# EnsembleOne.net
KiCad netlist of a schematic drawn in EAGLE
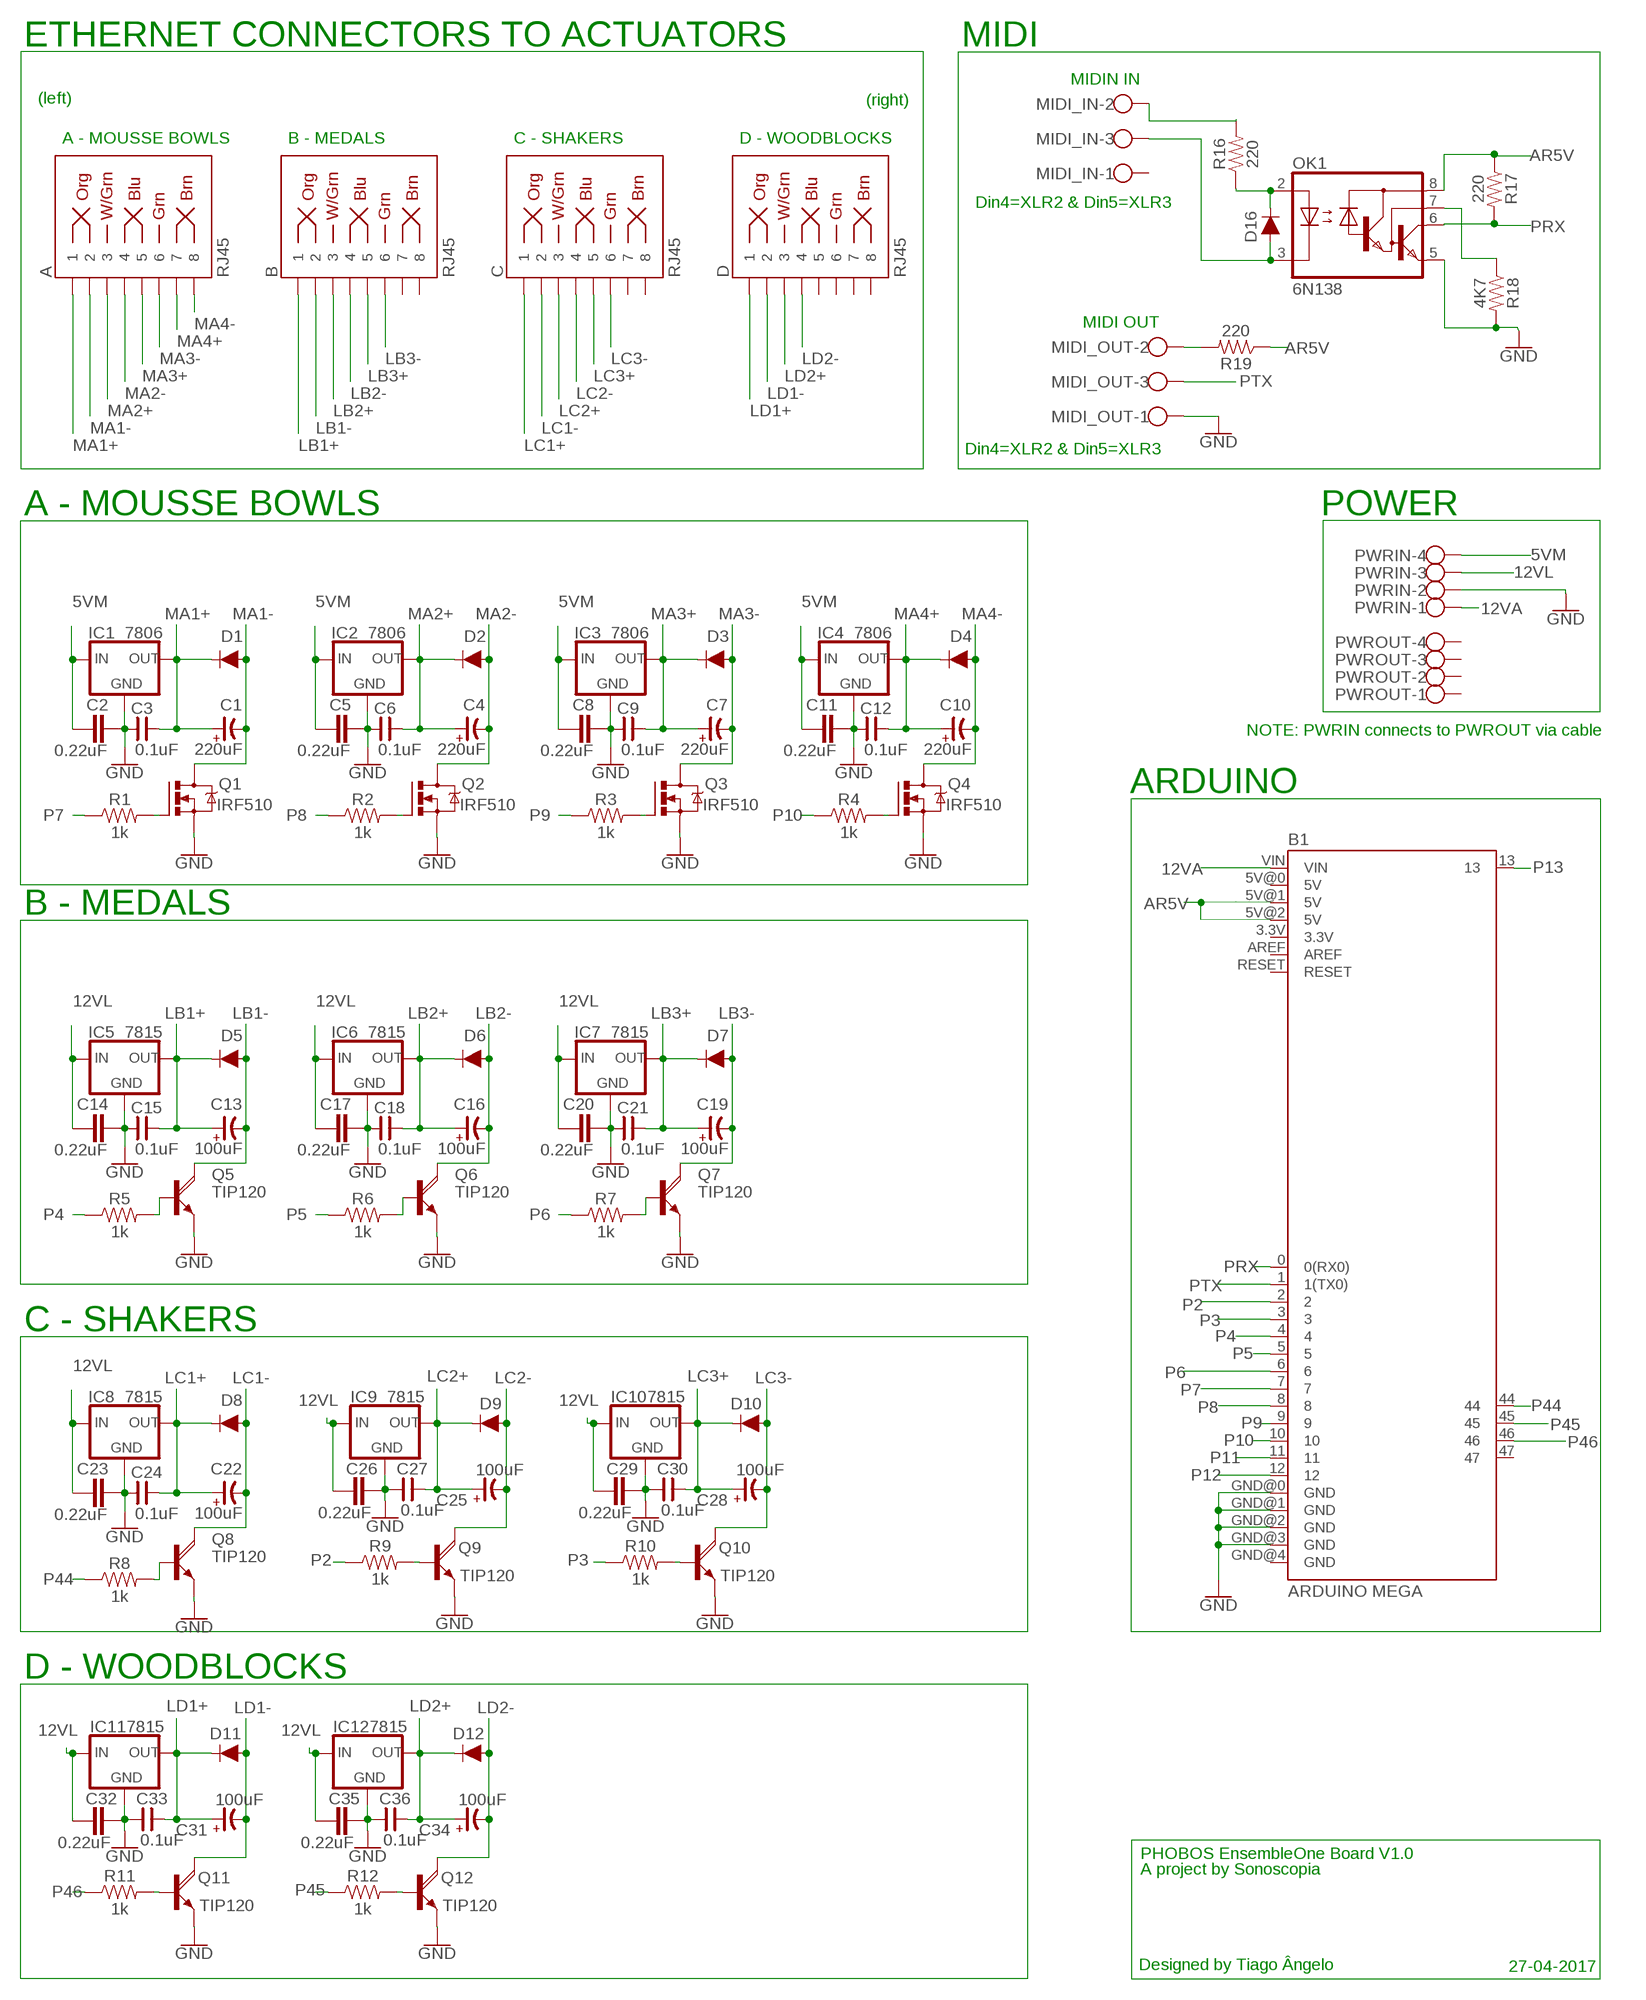
[diagram p0: schematic, sheet 1]

(export (version "E")
  (design (tool "Eeschema 10.0.6"))
  (components
    (comp (ref "A")
      (value "RJ45")
      (footprint "eagle-import:RJ45-8")
      (libsource (lib "eagle-import") (part "RJ45-8"))
    )
    (comp (ref "B")
      (value "RJ45")
      (footprint "eagle-import:RJ45-8")
      (libsource (lib "eagle-import") (part "RJ45-8"))
    )
    (comp (ref "B1")
      (value "ARDUINO MEGA")
      (footprint "eagle-import:ENSEMBLE_ONE_ARDUINO_MEGA")
      (libsource (lib "eagle-import") (part "ENSEMBLE_ONE_ARDUINO_MEGA_R3"))
    )
    (comp (ref "C")
      (value "RJ45")
      (footprint "eagle-import:RJ45-8")
      (libsource (lib "eagle-import") (part "RJ45-8"))
    )
    (comp (ref "C1")
      (value "220uF")
      (footprint "eagle-import:E-035X080")
      (libsource (lib "eagle-import") (part "CP-E-035X080"))
    )
    (comp (ref "C2")
      (value "0.22uF")
      (footprint "eagle-import:C5B3")
      (libsource (lib "eagle-import") (part "C5/3"))
    )
    (comp (ref "C3")
      (value "0.1uF")
      (footprint "eagle-import:C025-050X025")
      (libsource (lib "eagle-import") (part "CNP-C025-050X025"))
    )
    (comp (ref "C4")
      (value "220uF")
      (footprint "eagle-import:E-035X080")
      (libsource (lib "eagle-import") (part "CP-E-035X080"))
    )
    (comp (ref "C5")
      (value "0.22uF")
      (footprint "eagle-import:C5B3")
      (libsource (lib "eagle-import") (part "C5/3"))
    )
    (comp (ref "C6")
      (value "0.1uF")
      (footprint "eagle-import:C025-050X025")
      (libsource (lib "eagle-import") (part "CNP-C025-050X025"))
    )
    (comp (ref "C7")
      (value "220uF")
      (footprint "eagle-import:E-035X080")
      (libsource (lib "eagle-import") (part "CP-E-035X080"))
    )
    (comp (ref "C8")
      (value "0.22uF")
      (footprint "eagle-import:C5B3")
      (libsource (lib "eagle-import") (part "C5/3"))
    )
    (comp (ref "C9")
      (value "0.1uF")
      (footprint "eagle-import:C025-050X025")
      (libsource (lib "eagle-import") (part "CNP-C025-050X025"))
    )
    (comp (ref "C10")
      (value "220uF")
      (footprint "eagle-import:E-035X080")
      (libsource (lib "eagle-import") (part "CP-E-035X080"))
    )
    (comp (ref "C11")
      (value "0.22uF")
      (footprint "eagle-import:C5B3")
      (libsource (lib "eagle-import") (part "C5/3"))
    )
    (comp (ref "C12")
      (value "0.1uF")
      (footprint "eagle-import:C025-050X025")
      (libsource (lib "eagle-import") (part "CNP-C025-050X025"))
    )
    (comp (ref "C13")
      (value "100uF")
      (footprint "eagle-import:CAP-MASTER_E-020X050")
      (libsource (lib "eagle-import") (part "CAP-MASTER_CP-E-020X050"))
    )
    (comp (ref "C14")
      (value "0.22uF")
      (footprint "eagle-import:C5B3")
      (libsource (lib "eagle-import") (part "C5/3"))
    )
    (comp (ref "C15")
      (value "0.1uF")
      (footprint "eagle-import:C025-050X025")
      (libsource (lib "eagle-import") (part "CNP-C025-050X025"))
    )
    (comp (ref "C16")
      (value "100uF")
      (footprint "eagle-import:CAP-MASTER_E-020X050")
      (libsource (lib "eagle-import") (part "CAP-MASTER_CP-E-020X050"))
    )
    (comp (ref "C17")
      (value "0.22uF")
      (footprint "eagle-import:C5B3")
      (libsource (lib "eagle-import") (part "C5/3"))
    )
    (comp (ref "C18")
      (value "0.1uF")
      (footprint "eagle-import:C025-050X025")
      (libsource (lib "eagle-import") (part "CNP-C025-050X025"))
    )
    (comp (ref "C19")
      (value "100uF")
      (footprint "eagle-import:CAP-MASTER_E-020X050")
      (libsource (lib "eagle-import") (part "CAP-MASTER_CP-E-020X050"))
    )
    (comp (ref "C20")
      (value "0.22uF")
      (footprint "eagle-import:C5B3")
      (libsource (lib "eagle-import") (part "C5/3"))
    )
    (comp (ref "C21")
      (value "0.1uF")
      (footprint "eagle-import:C025-050X025")
      (libsource (lib "eagle-import") (part "CNP-C025-050X025"))
    )
    (comp (ref "C22")
      (value "100uF")
      (footprint "eagle-import:CAP-MASTER_E-020X050")
      (libsource (lib "eagle-import") (part "CAP-MASTER_CP-E-020X050"))
    )
    (comp (ref "C23")
      (value "0.22uF")
      (footprint "eagle-import:C5B3")
      (libsource (lib "eagle-import") (part "C5/3"))
    )
    (comp (ref "C24")
      (value "0.1uF")
      (footprint "eagle-import:C025-050X025")
      (libsource (lib "eagle-import") (part "CNP-C025-050X025"))
    )
    (comp (ref "C25")
      (value "100uF")
      (footprint "eagle-import:E-020X050")
      (libsource (lib "eagle-import") (part "CP-E-020X050"))
    )
    (comp (ref "C26")
      (value "0.22uF")
      (footprint "eagle-import:C5B3")
      (libsource (lib "eagle-import") (part "C5/3"))
    )
    (comp (ref "C27")
      (value "0.1uF")
      (footprint "eagle-import:C025-050X025")
      (libsource (lib "eagle-import") (part "CNP-C025-050X025"))
    )
    (comp (ref "C28")
      (value "100uF")
      (footprint "eagle-import:E-020X050")
      (libsource (lib "eagle-import") (part "CP-E-020X050"))
    )
    (comp (ref "C29")
      (value "0.22uF")
      (footprint "eagle-import:C5B3")
      (libsource (lib "eagle-import") (part "C5/3"))
    )
    (comp (ref "C30")
      (value "0.1uF")
      (footprint "eagle-import:C025-050X025")
      (libsource (lib "eagle-import") (part "CNP-C025-050X025"))
    )
    (comp (ref "C31")
      (value "100uF")
      (footprint "eagle-import:E-020X050")
      (libsource (lib "eagle-import") (part "CP-E-020X050"))
    )
    (comp (ref "C32")
      (value "0.22uF")
      (footprint "eagle-import:C5B3")
      (libsource (lib "eagle-import") (part "C5/3"))
    )
    (comp (ref "C33")
      (value "0.1uF")
      (footprint "eagle-import:C025-050X025")
      (libsource (lib "eagle-import") (part "CNP-C025-050X025"))
    )
    (comp (ref "C34")
      (value "100uF")
      (footprint "eagle-import:E-020X050")
      (libsource (lib "eagle-import") (part "CP-E-020X050"))
    )
    (comp (ref "C35")
      (value "0.22uF")
      (footprint "eagle-import:C5B3")
      (libsource (lib "eagle-import") (part "C5/3"))
    )
    (comp (ref "C36")
      (value "0.1uF")
      (footprint "eagle-import:C025-050X025")
      (libsource (lib "eagle-import") (part "CNP-C025-050X025"))
    )
    (comp (ref "D")
      (value "RJ45")
      (footprint "eagle-import:RJ45-8")
      (libsource (lib "eagle-import") (part "RJ45-8"))
    )
    (comp (ref "D1")
      (value "1A/50V/1.1V")
      (footprint "eagle-import:DIODE-1N4001-KIT")
      (libsource (lib "eagle-import") (part "DIODE-KIT2"))
    )
    (comp (ref "D2")
      (value "1A/50V/1.1V")
      (footprint "eagle-import:DIODE-1N4001-KIT")
      (libsource (lib "eagle-import") (part "DIODE-KIT2"))
    )
    (comp (ref "D3")
      (value "1A/50V/1.1V")
      (footprint "eagle-import:DIODE-1N4001-KIT")
      (libsource (lib "eagle-import") (part "DIODE-KIT2"))
    )
    (comp (ref "D4")
      (value "1A/50V/1.1V")
      (footprint "eagle-import:DIODE-1N4001-KIT")
      (libsource (lib "eagle-import") (part "DIODE-KIT2"))
    )
    (comp (ref "D5")
      (value "1A/50V/1.1V")
      (footprint "eagle-import:DIODE-1N4001-KIT")
      (libsource (lib "eagle-import") (part "DIODE-KIT2"))
    )
    (comp (ref "D6")
      (value "1A/50V/1.1V")
      (footprint "eagle-import:DIODE-1N4001-KIT")
      (libsource (lib "eagle-import") (part "DIODE-KIT2"))
    )
    (comp (ref "D7")
      (value "1A/50V/1.1V")
      (footprint "eagle-import:DIODE-1N4001-KIT")
      (libsource (lib "eagle-import") (part "DIODE-KIT2"))
    )
    (comp (ref "D8")
      (value "1A/50V/1.1V")
      (footprint "eagle-import:DIODE-1N4001-KIT")
      (libsource (lib "eagle-import") (part "DIODE-KIT2"))
    )
    (comp (ref "D9")
      (value "1A/50V/1.1V")
      (footprint "eagle-import:DIODE-1N4001-KIT")
      (libsource (lib "eagle-import") (part "DIODE-KIT2"))
    )
    (comp (ref "D10")
      (value "1A/50V/1.1V")
      (footprint "eagle-import:DIODE-1N4001-KIT")
      (libsource (lib "eagle-import") (part "DIODE-KIT2"))
    )
    (comp (ref "D11")
      (value "1A/50V/1.1V")
      (footprint "eagle-import:DIODE-1N4001-KIT")
      (libsource (lib "eagle-import") (part "DIODE-KIT2"))
    )
    (comp (ref "D12")
      (value "1A/50V/1.1V")
      (footprint "eagle-import:DIODE-1N4001-KIT")
      (libsource (lib "eagle-import") (part "DIODE-KIT2"))
    )
    (comp (ref "D16")
      (value "200mA/100V/1V")
      (footprint "eagle-import:DIODE-1N4148")
      (libsource (lib "eagle-import") (part "DIODE-1N4148"))
    )
    (comp (ref "IC1")
      (value "7806")
      (footprint "eagle-import:78XXS")
      (libsource (lib "eagle-import") (part "78XXS"))
    )
    (comp (ref "IC2")
      (value "7806")
      (footprint "eagle-import:78XXS")
      (libsource (lib "eagle-import") (part "78XXS"))
    )
    (comp (ref "IC3")
      (value "7806")
      (footprint "eagle-import:78XXS")
      (libsource (lib "eagle-import") (part "78XXS"))
    )
    (comp (ref "IC4")
      (value "7806")
      (footprint "eagle-import:78XXS")
      (libsource (lib "eagle-import") (part "78XXS"))
    )
    (comp (ref "IC5")
      (value "7815")
      (footprint "eagle-import:78XXS")
      (libsource (lib "eagle-import") (part "78XXS"))
    )
    (comp (ref "IC6")
      (value "7815")
      (footprint "eagle-import:78XXS")
      (libsource (lib "eagle-import") (part "78XXS"))
    )
    (comp (ref "IC7")
      (value "7815")
      (footprint "eagle-import:78XXS")
      (libsource (lib "eagle-import") (part "78XXS"))
    )
    (comp (ref "IC8")
      (value "7815")
      (footprint "eagle-import:78XXS")
      (libsource (lib "eagle-import") (part "78XXS"))
    )
    (comp (ref "IC9")
      (value "7815")
      (footprint "eagle-import:78XXS")
      (libsource (lib "eagle-import") (part "78XXS"))
    )
    (comp (ref "IC10")
      (value "7815")
      (footprint "eagle-import:78XXS")
      (libsource (lib "eagle-import") (part "78XXS"))
    )
    (comp (ref "IC11")
      (value "7815")
      (footprint "eagle-import:78XXS")
      (libsource (lib "eagle-import") (part "78XXS"))
    )
    (comp (ref "IC12")
      (value "7815")
      (footprint "eagle-import:78XXS")
      (libsource (lib "eagle-import") (part "78XXS"))
    )
    (comp (ref "MIDI_IN")
      (value "W237-103")
      (footprint "eagle-import:W237-103")
      (fields (field (name "MPN") "237-103"))
      (libsource (lib "eagle-import") (part "W237-103"))
    )
    (comp (ref "MIDI_OUT")
      (value "W237-103")
      (footprint "eagle-import:W237-103")
      (fields (field (name "MPN") "237-103"))
      (libsource (lib "eagle-import") (part "W237-103"))
    )
    (comp (ref "OK1")
      (value "6N138")
      (footprint "eagle-import:DIL08")
      (fields (field (name "MF") "VISHAY/TELEFUNKEN"))
      (libsource (lib "eagle-import") (part "6N138"))
    )
    (comp (ref "PWRIN")
      (value "W237-4")
      (footprint "eagle-import:W237-4")
      (libsource (lib "eagle-import") (part "W237-4"))
    )
    (comp (ref "PWROUT")
      (value "W237-4")
      (footprint "eagle-import:W237-4")
      (libsource (lib "eagle-import") (part "W237-4"))
    )
    (comp (ref "Q1")
      (value "IRF510")
      (footprint "eagle-import:TO220BV")
      (libsource (lib "eagle-import") (part "IRF520"))
    )
    (comp (ref "Q2")
      (value "IRF510")
      (footprint "eagle-import:TO220BV")
      (libsource (lib "eagle-import") (part "IRF520"))
    )
    (comp (ref "Q3")
      (value "IRF510")
      (footprint "eagle-import:TO220BV")
      (libsource (lib "eagle-import") (part "IRF520"))
    )
    (comp (ref "Q4")
      (value "IRF510")
      (footprint "eagle-import:TO220BV")
      (libsource (lib "eagle-import") (part "IRF520"))
    )
    (comp (ref "Q5")
      (value "TIP120")
      (footprint "eagle-import:ROCKETFARM_TO220AV")
      (libsource (lib "eagle-import") (part "ROCKETFARM_TIP120V"))
    )
    (comp (ref "Q6")
      (value "TIP120")
      (footprint "eagle-import:ROCKETFARM_TO220AV")
      (libsource (lib "eagle-import") (part "ROCKETFARM_TIP120V"))
    )
    (comp (ref "Q7")
      (value "TIP120")
      (footprint "eagle-import:ROCKETFARM_TO220AV")
      (libsource (lib "eagle-import") (part "ROCKETFARM_TIP120V"))
    )
    (comp (ref "Q8")
      (value "TIP120")
      (footprint "eagle-import:ROCKETFARM_TO220AV")
      (libsource (lib "eagle-import") (part "ROCKETFARM_TIP120V"))
    )
    (comp (ref "Q9")
      (value "TIP120")
      (footprint "eagle-import:TO220AV")
      (libsource (lib "eagle-import") (part "TIP120V"))
    )
    (comp (ref "Q10")
      (value "TIP120")
      (footprint "eagle-import:TO220AV")
      (libsource (lib "eagle-import") (part "TIP120V"))
    )
    (comp (ref "Q11")
      (value "TIP120")
      (footprint "eagle-import:TO220AV")
      (libsource (lib "eagle-import") (part "TIP120V"))
    )
    (comp (ref "Q12")
      (value "TIP120")
      (footprint "eagle-import:TO220AV")
      (libsource (lib "eagle-import") (part "TIP120V"))
    )
    (comp (ref "R1")
      (value "1k")
      (footprint "eagle-import:AXIAL-0.1")
      (libsource (lib "eagle-import") (part "1KOHM-VERT-1/4W-1%"))
    )
    (comp (ref "R2")
      (value "1k")
      (footprint "eagle-import:AXIAL-0.1")
      (libsource (lib "eagle-import") (part "1KOHM-VERT-1/4W-1%"))
    )
    (comp (ref "R3")
      (value "1k")
      (footprint "eagle-import:AXIAL-0.1")
      (libsource (lib "eagle-import") (part "1KOHM-VERT-1/4W-1%"))
    )
    (comp (ref "R4")
      (value "1k")
      (footprint "eagle-import:AXIAL-0.1")
      (libsource (lib "eagle-import") (part "1KOHM-VERT-1/4W-1%"))
    )
    (comp (ref "R5")
      (value "1k")
      (footprint "eagle-import:AXIAL-0.1")
      (libsource (lib "eagle-import") (part "1KOHM-VERT-1/4W-1%"))
    )
    (comp (ref "R6")
      (value "1k")
      (footprint "eagle-import:AXIAL-0.1")
      (libsource (lib "eagle-import") (part "1KOHM-VERT-1/4W-1%"))
    )
    (comp (ref "R7")
      (value "1k")
      (footprint "eagle-import:AXIAL-0.1")
      (libsource (lib "eagle-import") (part "1KOHM-VERT-1/4W-1%"))
    )
    (comp (ref "R8")
      (value "1k")
      (footprint "eagle-import:AXIAL-0.1")
      (libsource (lib "eagle-import") (part "1KOHM-VERT-1/4W-1%"))
    )
    (comp (ref "R9")
      (value "1k")
      (footprint "eagle-import:AXIAL-0.1")
      (libsource (lib "eagle-import") (part "1KOHM-VERT-1/4W-1%"))
    )
    (comp (ref "R10")
      (value "1k")
      (footprint "eagle-import:AXIAL-0.1")
      (libsource (lib "eagle-import") (part "1KOHM-VERT-1/4W-1%"))
    )
    (comp (ref "R11")
      (value "1k")
      (footprint "eagle-import:AXIAL-0.1")
      (libsource (lib "eagle-import") (part "1KOHM-VERT-1/4W-1%"))
    )
    (comp (ref "R12")
      (value "1k")
      (footprint "eagle-import:AXIAL-0.1")
      (libsource (lib "eagle-import") (part "1KOHM-VERT-1/4W-1%"))
    )
    (comp (ref "R16")
      (value "220")
      (footprint "eagle-import:AXIAL-0.3")
      (libsource (lib "eagle-import") (part "1KOHM-HORIZ-1/4W-5%"))
    )
    (comp (ref "R17")
      (value "220")
      (footprint "eagle-import:AXIAL-0.3")
      (libsource (lib "eagle-import") (part "1KOHM-HORIZ-1/4W-5%"))
    )
    (comp (ref "R18")
      (value "4K7")
      (footprint "eagle-import:AXIAL-0.3")
      (libsource (lib "eagle-import") (part "1KOHM-HORIZ-1/4W-5%"))
    )
    (comp (ref "R19")
      (value "220")
      (footprint "eagle-import:AXIAL-0.3")
      (libsource (lib "eagle-import") (part "1KOHM-HORIZ-1/4W-5%"))
    )
  )
  (nets
    (net (code "1") (name "/5VM") (class "Default")
      (node (ref "C11") (pin "1") (pinfunction "1_1") (pintype "passive"))
      (node (ref "C2") (pin "1") (pinfunction "1_1") (pintype "passive"))
      (node (ref "C5") (pin "1") (pinfunction "1_1") (pintype "passive"))
      (node (ref "C8") (pin "1") (pinfunction "1_1") (pintype "passive"))
      (node (ref "IC1") (pin "IN") (pinfunction "IN_IN") (pintype "input"))
      (node (ref "IC2") (pin "IN") (pinfunction "IN_IN") (pintype "input"))
      (node (ref "IC3") (pin "IN") (pinfunction "IN_IN") (pintype "input"))
      (node (ref "IC4") (pin "IN") (pinfunction "IN_IN") (pintype "input"))
      (node (ref "PWRIN") (pin "4") (pinfunction "KL_4") (pintype "passive"))
    )
    (net (code "2") (name "/12VA") (class "Default")
      (node (ref "B1") (pin "VIN") (pinfunction "VIN_VIN") (pintype "bidirectional"))
      (node (ref "PWRIN") (pin "1") (pinfunction "KL_1") (pintype "passive"))
    )
    (net (code "3") (name "/12VL") (class "Default")
      (node (ref "C14") (pin "1") (pinfunction "1_1") (pintype "passive"))
      (node (ref "C17") (pin "1") (pinfunction "1_1") (pintype "passive"))
      (node (ref "C20") (pin "1") (pinfunction "1_1") (pintype "passive"))
      (node (ref "C23") (pin "1") (pinfunction "1_1") (pintype "passive"))
      (node (ref "C26") (pin "1") (pinfunction "1_1") (pintype "passive"))
      (node (ref "C29") (pin "1") (pinfunction "1_1") (pintype "passive"))
      (node (ref "C32") (pin "1") (pinfunction "1_1") (pintype "passive"))
      (node (ref "C35") (pin "1") (pinfunction "1_1") (pintype "passive"))
      (node (ref "IC10") (pin "IN") (pinfunction "IN_IN") (pintype "input"))
      (node (ref "IC11") (pin "IN") (pinfunction "IN_IN") (pintype "input"))
      (node (ref "IC12") (pin "IN") (pinfunction "IN_IN") (pintype "input"))
      (node (ref "IC5") (pin "IN") (pinfunction "IN_IN") (pintype "input"))
      (node (ref "IC6") (pin "IN") (pinfunction "IN_IN") (pintype "input"))
      (node (ref "IC7") (pin "IN") (pinfunction "IN_IN") (pintype "input"))
      (node (ref "IC8") (pin "IN") (pinfunction "IN_IN") (pintype "input"))
      (node (ref "IC9") (pin "IN") (pinfunction "IN_IN") (pintype "input"))
      (node (ref "PWRIN") (pin "3") (pinfunction "KL_3") (pintype "passive"))
    )
    (net (code "4") (name "/AR5V") (class "Default")
      (node (ref "B1") (pin "5V@1") (pinfunction "5V_5V@1") (pintype "bidirectional"))
      (node (ref "B1") (pin "5V@2") (pinfunction "5V_5V@2") (pintype "bidirectional"))
      (node (ref "OK1") (pin "8") (pinfunction "VCC_8") (pintype "passive"))
      (node (ref "R17") (pin "P$1") (pinfunction "1_P$1") (pintype "passive"))
      (node (ref "R19") (pin "P$1") (pinfunction "1_P$1") (pintype "passive"))
    )
    (net (code "5") (name "/LB1+") (class "Default")
      (node (ref "B") (pin "1") (pinfunction "1_1") (pintype "bidirectional"))
      (node (ref "C13") (pin "+") (pinfunction "+_+") (pintype "passive"))
      (node (ref "C15") (pin "2") (pinfunction "2_2") (pintype "passive"))
      (node (ref "D5") (pin "C") (pinfunction "C_C") (pintype "passive"))
      (node (ref "IC5") (pin "OUT") (pinfunction "OUT_OUT") (pintype "passive"))
    )
    (net (code "6") (name "/LB1-") (class "Default")
      (node (ref "B") (pin "2") (pinfunction "2_2") (pintype "bidirectional"))
      (node (ref "C13") (pin "-") (pinfunction "-_-") (pintype "passive"))
      (node (ref "D5") (pin "A") (pinfunction "A_A") (pintype "passive"))
      (node (ref "Q5") (pin "C") (pinfunction "C_C") (pintype "passive"))
    )
    (net (code "7") (name "/LB2+") (class "Default")
      (node (ref "B") (pin "3") (pinfunction "3_3") (pintype "bidirectional"))
      (node (ref "C16") (pin "+") (pinfunction "+_+") (pintype "passive"))
      (node (ref "C18") (pin "2") (pinfunction "2_2") (pintype "passive"))
      (node (ref "D6") (pin "C") (pinfunction "C_C") (pintype "passive"))
      (node (ref "IC6") (pin "OUT") (pinfunction "OUT_OUT") (pintype "passive"))
    )
    (net (code "8") (name "/LB2-") (class "Default")
      (node (ref "B") (pin "4") (pinfunction "4_4") (pintype "bidirectional"))
      (node (ref "C16") (pin "-") (pinfunction "-_-") (pintype "passive"))
      (node (ref "D6") (pin "A") (pinfunction "A_A") (pintype "passive"))
      (node (ref "Q6") (pin "C") (pinfunction "C_C") (pintype "passive"))
    )
    (net (code "9") (name "/LB3+") (class "Default")
      (node (ref "B") (pin "5") (pinfunction "5_5") (pintype "bidirectional"))
      (node (ref "C19") (pin "+") (pinfunction "+_+") (pintype "passive"))
      (node (ref "C21") (pin "2") (pinfunction "2_2") (pintype "passive"))
      (node (ref "D7") (pin "C") (pinfunction "C_C") (pintype "passive"))
      (node (ref "IC7") (pin "OUT") (pinfunction "OUT_OUT") (pintype "passive"))
    )
    (net (code "10") (name "/LB3-") (class "Default")
      (node (ref "B") (pin "6") (pinfunction "6_6") (pintype "bidirectional"))
      (node (ref "C19") (pin "-") (pinfunction "-_-") (pintype "passive"))
      (node (ref "D7") (pin "A") (pinfunction "A_A") (pintype "passive"))
      (node (ref "Q7") (pin "C") (pinfunction "C_C") (pintype "passive"))
    )
    (net (code "11") (name "/LC1+") (class "Default")
      (node (ref "C") (pin "1") (pinfunction "1_1") (pintype "bidirectional"))
      (node (ref "C22") (pin "+") (pinfunction "+_+") (pintype "passive"))
      (node (ref "C24") (pin "2") (pinfunction "2_2") (pintype "passive"))
      (node (ref "D8") (pin "C") (pinfunction "C_C") (pintype "passive"))
      (node (ref "IC8") (pin "OUT") (pinfunction "OUT_OUT") (pintype "passive"))
    )
    (net (code "12") (name "/LC1-") (class "Default")
      (node (ref "C") (pin "2") (pinfunction "2_2") (pintype "bidirectional"))
      (node (ref "C22") (pin "-") (pinfunction "-_-") (pintype "passive"))
      (node (ref "D8") (pin "A") (pinfunction "A_A") (pintype "passive"))
      (node (ref "Q8") (pin "C") (pinfunction "C_C") (pintype "passive"))
    )
    (net (code "13") (name "/LC2+") (class "Default")
      (node (ref "C") (pin "3") (pinfunction "3_3") (pintype "bidirectional"))
      (node (ref "C25") (pin "+") (pinfunction "+_+") (pintype "passive"))
      (node (ref "C27") (pin "2") (pinfunction "2_2") (pintype "passive"))
      (node (ref "D9") (pin "C") (pinfunction "C_C") (pintype "passive"))
      (node (ref "IC9") (pin "OUT") (pinfunction "OUT_OUT") (pintype "passive"))
    )
    (net (code "14") (name "/LC2-") (class "Default")
      (node (ref "C") (pin "4") (pinfunction "4_4") (pintype "bidirectional"))
      (node (ref "C25") (pin "-") (pinfunction "-_-") (pintype "passive"))
      (node (ref "D9") (pin "A") (pinfunction "A_A") (pintype "passive"))
      (node (ref "Q9") (pin "C") (pinfunction "C_C") (pintype "passive"))
    )
    (net (code "15") (name "/LC3+") (class "Default")
      (node (ref "C") (pin "5") (pinfunction "5_5") (pintype "bidirectional"))
      (node (ref "C28") (pin "+") (pinfunction "+_+") (pintype "passive"))
      (node (ref "C30") (pin "2") (pinfunction "2_2") (pintype "passive"))
      (node (ref "D10") (pin "C") (pinfunction "C_C") (pintype "passive"))
      (node (ref "IC10") (pin "OUT") (pinfunction "OUT_OUT") (pintype "passive"))
    )
    (net (code "16") (name "/LC3-") (class "Default")
      (node (ref "C") (pin "6") (pinfunction "6_6") (pintype "bidirectional"))
      (node (ref "C28") (pin "-") (pinfunction "-_-") (pintype "passive"))
      (node (ref "D10") (pin "A") (pinfunction "A_A") (pintype "passive"))
      (node (ref "Q10") (pin "C") (pinfunction "C_C") (pintype "passive"))
    )
    (net (code "17") (name "/LD1+") (class "Default")
      (node (ref "C31") (pin "+") (pinfunction "+_+") (pintype "passive"))
      (node (ref "C33") (pin "2") (pinfunction "2_2") (pintype "passive"))
      (node (ref "D") (pin "1") (pinfunction "1_1") (pintype "bidirectional"))
      (node (ref "D11") (pin "C") (pinfunction "C_C") (pintype "passive"))
      (node (ref "IC11") (pin "OUT") (pinfunction "OUT_OUT") (pintype "passive"))
    )
    (net (code "18") (name "/LD1-") (class "Default")
      (node (ref "C31") (pin "-") (pinfunction "-_-") (pintype "passive"))
      (node (ref "D") (pin "2") (pinfunction "2_2") (pintype "bidirectional"))
      (node (ref "D11") (pin "A") (pinfunction "A_A") (pintype "passive"))
      (node (ref "Q11") (pin "C") (pinfunction "C_C") (pintype "passive"))
    )
    (net (code "19") (name "/LD2+") (class "Default")
      (node (ref "C34") (pin "+") (pinfunction "+_+") (pintype "passive"))
      (node (ref "C36") (pin "2") (pinfunction "2_2") (pintype "passive"))
      (node (ref "D") (pin "3") (pinfunction "3_3") (pintype "bidirectional"))
      (node (ref "D12") (pin "C") (pinfunction "C_C") (pintype "passive"))
      (node (ref "IC12") (pin "OUT") (pinfunction "OUT_OUT") (pintype "passive"))
    )
    (net (code "20") (name "/LD2-") (class "Default")
      (node (ref "C34") (pin "-") (pinfunction "-_-") (pintype "passive"))
      (node (ref "D") (pin "4") (pinfunction "4_4") (pintype "bidirectional"))
      (node (ref "D12") (pin "A") (pinfunction "A_A") (pintype "passive"))
      (node (ref "Q12") (pin "C") (pinfunction "C_C") (pintype "passive"))
    )
    (net (code "21") (name "/MA1+") (class "Default")
      (node (ref "A") (pin "1") (pinfunction "1_1") (pintype "bidirectional"))
      (node (ref "C1") (pin "+") (pinfunction "+_+") (pintype "passive"))
      (node (ref "C3") (pin "2") (pinfunction "2_2") (pintype "passive"))
      (node (ref "D1") (pin "C") (pinfunction "C_C") (pintype "passive"))
      (node (ref "IC1") (pin "OUT") (pinfunction "OUT_OUT") (pintype "passive"))
    )
    (net (code "22") (name "/MA1-") (class "Default")
      (node (ref "A") (pin "2") (pinfunction "2_2") (pintype "bidirectional"))
      (node (ref "C1") (pin "-") (pinfunction "-_-") (pintype "passive"))
      (node (ref "D1") (pin "A") (pinfunction "A_A") (pintype "passive"))
      (node (ref "Q1") (pin "D") (pinfunction "D_D") (pintype "passive"))
    )
    (net (code "23") (name "/MA2+") (class "Default")
      (node (ref "A") (pin "3") (pinfunction "3_3") (pintype "bidirectional"))
      (node (ref "C4") (pin "+") (pinfunction "+_+") (pintype "passive"))
      (node (ref "C6") (pin "2") (pinfunction "2_2") (pintype "passive"))
      (node (ref "D2") (pin "C") (pinfunction "C_C") (pintype "passive"))
      (node (ref "IC2") (pin "OUT") (pinfunction "OUT_OUT") (pintype "passive"))
    )
    (net (code "24") (name "/MA2-") (class "Default")
      (node (ref "A") (pin "4") (pinfunction "4_4") (pintype "bidirectional"))
      (node (ref "C4") (pin "-") (pinfunction "-_-") (pintype "passive"))
      (node (ref "D2") (pin "A") (pinfunction "A_A") (pintype "passive"))
      (node (ref "Q2") (pin "D") (pinfunction "D_D") (pintype "passive"))
    )
    (net (code "25") (name "/MA3+") (class "Default")
      (node (ref "A") (pin "5") (pinfunction "5_5") (pintype "bidirectional"))
      (node (ref "C7") (pin "+") (pinfunction "+_+") (pintype "passive"))
      (node (ref "C9") (pin "2") (pinfunction "2_2") (pintype "passive"))
      (node (ref "D3") (pin "C") (pinfunction "C_C") (pintype "passive"))
      (node (ref "IC3") (pin "OUT") (pinfunction "OUT_OUT") (pintype "passive"))
    )
    (net (code "26") (name "/MA3-") (class "Default")
      (node (ref "A") (pin "6") (pinfunction "6_6") (pintype "bidirectional"))
      (node (ref "C7") (pin "-") (pinfunction "-_-") (pintype "passive"))
      (node (ref "D3") (pin "A") (pinfunction "A_A") (pintype "passive"))
      (node (ref "Q3") (pin "D") (pinfunction "D_D") (pintype "passive"))
    )
    (net (code "27") (name "/MA4+") (class "Default")
      (node (ref "A") (pin "7") (pinfunction "7_7") (pintype "bidirectional"))
      (node (ref "C10") (pin "+") (pinfunction "+_+") (pintype "passive"))
      (node (ref "C12") (pin "2") (pinfunction "2_2") (pintype "passive"))
      (node (ref "D4") (pin "C") (pinfunction "C_C") (pintype "passive"))
      (node (ref "IC4") (pin "OUT") (pinfunction "OUT_OUT") (pintype "passive"))
    )
    (net (code "28") (name "/MA4-") (class "Default")
      (node (ref "A") (pin "8") (pinfunction "8_8") (pintype "bidirectional"))
      (node (ref "C10") (pin "-") (pinfunction "-_-") (pintype "passive"))
      (node (ref "D4") (pin "A") (pinfunction "A_A") (pintype "passive"))
      (node (ref "Q4") (pin "D") (pinfunction "D_D") (pintype "passive"))
    )
    (net (code "29") (name "/P2") (class "Default")
      (node (ref "B1") (pin "2") (pinfunction "2_2") (pintype "bidirectional"))
      (node (ref "R9") (pin "P$1") (pinfunction "1_P$1") (pintype "passive"))
    )
    (net (code "30") (name "/P3") (class "Default")
      (node (ref "B1") (pin "3") (pinfunction "3_3") (pintype "bidirectional"))
      (node (ref "R10") (pin "P$1") (pinfunction "1_P$1") (pintype "passive"))
    )
    (net (code "31") (name "/P4") (class "Default")
      (node (ref "B1") (pin "4") (pinfunction "4_4") (pintype "bidirectional"))
      (node (ref "R5") (pin "P$1") (pinfunction "1_P$1") (pintype "passive"))
    )
    (net (code "32") (name "/P5") (class "Default")
      (node (ref "B1") (pin "5") (pinfunction "5_5") (pintype "bidirectional"))
      (node (ref "R6") (pin "P$1") (pinfunction "1_P$1") (pintype "passive"))
    )
    (net (code "33") (name "/P6") (class "Default")
      (node (ref "B1") (pin "6") (pinfunction "6_6") (pintype "bidirectional"))
      (node (ref "R7") (pin "P$1") (pinfunction "1_P$1") (pintype "passive"))
    )
    (net (code "34") (name "/P7") (class "Default")
      (node (ref "B1") (pin "7") (pinfunction "7_7") (pintype "bidirectional"))
      (node (ref "R1") (pin "P$1") (pinfunction "1_P$1") (pintype "passive"))
    )
    (net (code "35") (name "/P8") (class "Default")
      (node (ref "B1") (pin "8") (pinfunction "8_8") (pintype "bidirectional"))
      (node (ref "R2") (pin "P$1") (pinfunction "1_P$1") (pintype "passive"))
    )
    (net (code "36") (name "/P9") (class "Default")
      (node (ref "B1") (pin "9") (pinfunction "9_9") (pintype "bidirectional"))
      (node (ref "R3") (pin "P$1") (pinfunction "1_P$1") (pintype "passive"))
    )
    (net (code "37") (name "/P10") (class "Default")
      (node (ref "B1") (pin "10") (pinfunction "10_10") (pintype "bidirectional"))
      (node (ref "R4") (pin "P$1") (pinfunction "1_P$1") (pintype "passive"))
    )
    (net (code "38") (name "/P11") (class "Default")
      (node (ref "B1") (pin "11") (pinfunction "11_11") (pintype "bidirectional"))
    )
    (net (code "39") (name "/P12") (class "Default")
      (node (ref "B1") (pin "12") (pinfunction "12_12") (pintype "bidirectional"))
    )
    (net (code "40") (name "/P13") (class "Default")
      (node (ref "B1") (pin "13") (pinfunction "13_13") (pintype "bidirectional"))
    )
    (net (code "41") (name "/P44") (class "Default")
      (node (ref "B1") (pin "44") (pinfunction "44_44") (pintype "bidirectional"))
      (node (ref "R8") (pin "P$1") (pinfunction "1_P$1") (pintype "passive"))
    )
    (net (code "42") (name "/P45") (class "Default")
      (node (ref "B1") (pin "45") (pinfunction "45_45") (pintype "bidirectional"))
      (node (ref "R12") (pin "P$1") (pinfunction "1_P$1") (pintype "passive"))
    )
    (net (code "43") (name "/P46") (class "Default")
      (node (ref "B1") (pin "46") (pinfunction "46_46") (pintype "bidirectional"))
      (node (ref "R11") (pin "P$1") (pinfunction "1_P$1") (pintype "passive"))
    )
    (net (code "44") (name "/PRX") (class "Default")
      (node (ref "B1") (pin "0") (pinfunction "0(RX0)_0") (pintype "bidirectional"))
      (node (ref "OK1") (pin "6") (pinfunction "VO_6") (pintype "passive"))
      (node (ref "R17") (pin "P$2") (pinfunction "2_P$2") (pintype "passive"))
    )
    (net (code "45") (name "/PTX") (class "Default")
      (node (ref "B1") (pin "1") (pinfunction "1(TX0)_1") (pintype "bidirectional"))
      (node (ref "MIDI_OUT") (pin "3") (pinfunction "KL_3") (pintype "passive"))
    )
    (net (code "46") (name "GND") (class "Default")
      (node (ref "B1") (pin "GND@0") (pinfunction "GND_GND@0") (pintype "bidirectional"))
      (node (ref "B1") (pin "GND@1") (pinfunction "GND_GND@1") (pintype "bidirectional"))
      (node (ref "B1") (pin "GND@2") (pinfunction "GND_GND@2") (pintype "bidirectional"))
      (node (ref "B1") (pin "GND@3") (pinfunction "GND_GND@3") (pintype "bidirectional"))
      (node (ref "C11") (pin "2") (pinfunction "2_2") (pintype "passive"))
      (node (ref "C12") (pin "1") (pinfunction "1_1") (pintype "passive"))
      (node (ref "C14") (pin "2") (pinfunction "2_2") (pintype "passive"))
      (node (ref "C15") (pin "1") (pinfunction "1_1") (pintype "passive"))
      (node (ref "C17") (pin "2") (pinfunction "2_2") (pintype "passive"))
      (node (ref "C18") (pin "1") (pinfunction "1_1") (pintype "passive"))
      (node (ref "C2") (pin "2") (pinfunction "2_2") (pintype "passive"))
      (node (ref "C20") (pin "2") (pinfunction "2_2") (pintype "passive"))
      (node (ref "C21") (pin "1") (pinfunction "1_1") (pintype "passive"))
      (node (ref "C23") (pin "2") (pinfunction "2_2") (pintype "passive"))
      (node (ref "C24") (pin "1") (pinfunction "1_1") (pintype "passive"))
      (node (ref "C26") (pin "2") (pinfunction "2_2") (pintype "passive"))
      (node (ref "C27") (pin "1") (pinfunction "1_1") (pintype "passive"))
      (node (ref "C29") (pin "2") (pinfunction "2_2") (pintype "passive"))
      (node (ref "C3") (pin "1") (pinfunction "1_1") (pintype "passive"))
      (node (ref "C30") (pin "1") (pinfunction "1_1") (pintype "passive"))
      (node (ref "C32") (pin "2") (pinfunction "2_2") (pintype "passive"))
      (node (ref "C33") (pin "1") (pinfunction "1_1") (pintype "passive"))
      (node (ref "C35") (pin "2") (pinfunction "2_2") (pintype "passive"))
      (node (ref "C36") (pin "1") (pinfunction "1_1") (pintype "passive"))
      (node (ref "C5") (pin "2") (pinfunction "2_2") (pintype "passive"))
      (node (ref "C6") (pin "1") (pinfunction "1_1") (pintype "passive"))
      (node (ref "C8") (pin "2") (pinfunction "2_2") (pintype "passive"))
      (node (ref "C9") (pin "1") (pinfunction "1_1") (pintype "passive"))
      (node (ref "IC1") (pin "GND") (pinfunction "GND_GND") (pintype "input"))
      (node (ref "IC10") (pin "GND") (pinfunction "GND_GND") (pintype "input"))
      (node (ref "IC11") (pin "GND") (pinfunction "GND_GND") (pintype "input"))
      (node (ref "IC12") (pin "GND") (pinfunction "GND_GND") (pintype "input"))
      (node (ref "IC2") (pin "GND") (pinfunction "GND_GND") (pintype "input"))
      (node (ref "IC3") (pin "GND") (pinfunction "GND_GND") (pintype "input"))
      (node (ref "IC4") (pin "GND") (pinfunction "GND_GND") (pintype "input"))
      (node (ref "IC5") (pin "GND") (pinfunction "GND_GND") (pintype "input"))
      (node (ref "IC6") (pin "GND") (pinfunction "GND_GND") (pintype "input"))
      (node (ref "IC7") (pin "GND") (pinfunction "GND_GND") (pintype "input"))
      (node (ref "IC8") (pin "GND") (pinfunction "GND_GND") (pintype "input"))
      (node (ref "IC9") (pin "GND") (pinfunction "GND_GND") (pintype "input"))
      (node (ref "MIDI_OUT") (pin "1") (pinfunction "KL_1") (pintype "passive"))
      (node (ref "OK1") (pin "5") (pinfunction "GND_5") (pintype "passive"))
      (node (ref "PWRIN") (pin "2") (pinfunction "KL_2") (pintype "passive"))
      (node (ref "Q1") (pin "S") (pinfunction "S_S") (pintype "passive"))
      (node (ref "Q10") (pin "E") (pinfunction "E_E") (pintype "passive"))
      (node (ref "Q11") (pin "E") (pinfunction "E_E") (pintype "passive"))
      (node (ref "Q12") (pin "E") (pinfunction "E_E") (pintype "passive"))
      (node (ref "Q2") (pin "S") (pinfunction "S_S") (pintype "passive"))
      (node (ref "Q3") (pin "S") (pinfunction "S_S") (pintype "passive"))
      (node (ref "Q4") (pin "S") (pinfunction "S_S") (pintype "passive"))
      (node (ref "Q5") (pin "E") (pinfunction "E_E") (pintype "passive"))
      (node (ref "Q6") (pin "E") (pinfunction "E_E") (pintype "passive"))
      (node (ref "Q7") (pin "E") (pinfunction "E_E") (pintype "passive"))
      (node (ref "Q8") (pin "E") (pinfunction "E_E") (pintype "passive"))
      (node (ref "Q9") (pin "E") (pinfunction "E_E") (pintype "passive"))
      (node (ref "R18") (pin "P$2") (pinfunction "2_P$2") (pintype "passive"))
    )
    (net (code "47") (name "Net-(MIDI_INB-KL)") (class "Default")
      (node (ref "MIDI_IN") (pin "2") (pinfunction "KL_2") (pintype "passive"))
      (node (ref "R16") (pin "P$2") (pinfunction "2_P$2") (pintype "passive"))
    )
    (net (code "48") (name "Net-(MIDI_INC-KL)") (class "Default")
      (node (ref "D16") (pin "A") (pinfunction "A_A") (pintype "passive"))
      (node (ref "MIDI_IN") (pin "3") (pinfunction "KL_3") (pintype "passive"))
      (node (ref "OK1") (pin "3") (pinfunction "C_3") (pintype "passive"))
    )
    (net (code "49") (name "Net-(MIDI_OUTB-KL)") (class "Default")
      (node (ref "MIDI_OUT") (pin "2") (pinfunction "KL_2") (pintype "passive"))
      (node (ref "R19") (pin "P$2") (pinfunction "2_P$2") (pintype "passive"))
    )
    (net (code "50") (name "Net-(OK1-A)") (class "Default")
      (node (ref "D16") (pin "C") (pinfunction "C_C") (pintype "passive"))
      (node (ref "OK1") (pin "2") (pinfunction "A_2") (pintype "passive"))
      (node (ref "R16") (pin "P$1") (pinfunction "1_P$1") (pintype "passive"))
    )
    (net (code "51") (name "Net-(OK1-VB)") (class "Default")
      (node (ref "OK1") (pin "7") (pinfunction "VB_7") (pintype "passive"))
      (node (ref "R18") (pin "P$1") (pinfunction "1_P$1") (pintype "passive"))
    )
    (net (code "52") (name "Net-(R1-2)") (class "Default")
      (node (ref "Q1") (pin "G") (pinfunction "G_G") (pintype "passive"))
      (node (ref "R1") (pin "P$2") (pinfunction "2_P$2") (pintype "passive"))
    )
    (net (code "53") (name "Net-(R2-2)") (class "Default")
      (node (ref "Q2") (pin "G") (pinfunction "G_G") (pintype "passive"))
      (node (ref "R2") (pin "P$2") (pinfunction "2_P$2") (pintype "passive"))
    )
    (net (code "54") (name "Net-(R3-2)") (class "Default")
      (node (ref "Q3") (pin "G") (pinfunction "G_G") (pintype "passive"))
      (node (ref "R3") (pin "P$2") (pinfunction "2_P$2") (pintype "passive"))
    )
    (net (code "55") (name "Net-(R4-2)") (class "Default")
      (node (ref "Q4") (pin "G") (pinfunction "G_G") (pintype "passive"))
      (node (ref "R4") (pin "P$2") (pinfunction "2_P$2") (pintype "passive"))
    )
    (net (code "56") (name "Net-(R5-2)") (class "Default")
      (node (ref "Q5") (pin "B") (pinfunction "B_B") (pintype "passive"))
      (node (ref "R5") (pin "P$2") (pinfunction "2_P$2") (pintype "passive"))
    )
    (net (code "57") (name "Net-(R6-2)") (class "Default")
      (node (ref "Q6") (pin "B") (pinfunction "B_B") (pintype "passive"))
      (node (ref "R6") (pin "P$2") (pinfunction "2_P$2") (pintype "passive"))
    )
    (net (code "58") (name "Net-(R7-2)") (class "Default")
      (node (ref "Q7") (pin "B") (pinfunction "B_B") (pintype "passive"))
      (node (ref "R7") (pin "P$2") (pinfunction "2_P$2") (pintype "passive"))
    )
    (net (code "59") (name "Net-(R8-2)") (class "Default")
      (node (ref "Q8") (pin "B") (pinfunction "B_B") (pintype "passive"))
      (node (ref "R8") (pin "P$2") (pinfunction "2_P$2") (pintype "passive"))
    )
    (net (code "60") (name "Net-(R9-2)") (class "Default")
      (node (ref "Q9") (pin "B") (pinfunction "B_B") (pintype "passive"))
      (node (ref "R9") (pin "P$2") (pinfunction "2_P$2") (pintype "passive"))
    )
    (net (code "61") (name "Net-(R10-2)") (class "Default")
      (node (ref "Q10") (pin "B") (pinfunction "B_B") (pintype "passive"))
      (node (ref "R10") (pin "P$2") (pinfunction "2_P$2") (pintype "passive"))
    )
    (net (code "62") (name "Net-(R11-2)") (class "Default")
      (node (ref "Q11") (pin "B") (pinfunction "B_B") (pintype "passive"))
      (node (ref "R11") (pin "P$2") (pinfunction "2_P$2") (pintype "passive"))
    )
    (net (code "63") (name "Net-(R12-2)") (class "Default")
      (node (ref "Q12") (pin "B") (pinfunction "B_B") (pintype "passive"))
      (node (ref "R12") (pin "P$2") (pinfunction "2_P$2") (pintype "passive"))
    )
    (net (code "64") (name "unconnected-(B-Pad7)") (class "Default")
      (node (ref "B") (pin "7") (pinfunction "7_7") (pintype "bidirectional"))
    )
    (net (code "65") (name "unconnected-(B-Pad8)") (class "Default")
      (node (ref "B") (pin "8") (pinfunction "8_8") (pintype "bidirectional"))
    )
    (net (code "66") (name "unconnected-(B1-5V-Pad5V@0)") (class "Default")
      (node (ref "B1") (pin "5V@0") (pinfunction "5V_5V@0") (pintype "bidirectional"))
    )
    (net (code "67") (name "unconnected-(B1-GND-PadGND@4)") (class "Default")
      (node (ref "B1") (pin "GND@4") (pinfunction "GND_GND@4") (pintype "bidirectional"))
    )
    (net (code "68") (name "unconnected-(B1-Pad3.3V)") (class "Default")
      (node (ref "B1") (pin "3.3V") (pinfunction "3.3V_3.3V") (pintype "bidirectional"))
    )
    (net (code "69") (name "unconnected-(B1-Pad47)") (class "Default")
      (node (ref "B1") (pin "47") (pinfunction "47_47") (pintype "bidirectional"))
    )
    (net (code "70") (name "unconnected-(B1-PadAREF)") (class "Default")
      (node (ref "B1") (pin "AREF") (pinfunction "AREF_AREF") (pintype "bidirectional"))
    )
    (net (code "71") (name "unconnected-(B1-PadRESET)") (class "Default")
      (node (ref "B1") (pin "RESET") (pinfunction "RESET_RESET") (pintype "bidirectional"))
    )
    (net (code "72") (name "unconnected-(C-Pad7)") (class "Default")
      (node (ref "C") (pin "7") (pinfunction "7_7") (pintype "bidirectional"))
    )
    (net (code "73") (name "unconnected-(C-Pad8)") (class "Default")
      (node (ref "C") (pin "8") (pinfunction "8_8") (pintype "bidirectional"))
    )
    (net (code "74") (name "unconnected-(D-Pad5)") (class "Default")
      (node (ref "D") (pin "5") (pinfunction "5_5") (pintype "bidirectional"))
    )
    (net (code "75") (name "unconnected-(D-Pad6)") (class "Default")
      (node (ref "D") (pin "6") (pinfunction "6_6") (pintype "bidirectional"))
    )
    (net (code "76") (name "unconnected-(D-Pad7)") (class "Default")
      (node (ref "D") (pin "7") (pinfunction "7_7") (pintype "bidirectional"))
    )
    (net (code "77") (name "unconnected-(D-Pad8)") (class "Default")
      (node (ref "D") (pin "8") (pinfunction "8_8") (pintype "bidirectional"))
    )
    (net (code "78") (name "unconnected-(MIDI_INA-KL-Pad1)") (class "Default")
      (node (ref "MIDI_IN") (pin "1") (pinfunction "KL_1") (pintype "passive"))
    )
    (net (code "79") (name "unconnected-(PWROUTA-KL-Pad1)") (class "Default")
      (node (ref "PWROUT") (pin "1") (pinfunction "KL_1") (pintype "passive"))
    )
    (net (code "80") (name "unconnected-(PWROUTB-KL-Pad2)") (class "Default")
      (node (ref "PWROUT") (pin "2") (pinfunction "KL_2") (pintype "passive"))
    )
    (net (code "81") (name "unconnected-(PWROUTC-KL-Pad3)") (class "Default")
      (node (ref "PWROUT") (pin "3") (pinfunction "KL_3") (pintype "passive"))
    )
    (net (code "82") (name "unconnected-(PWROUTD-KL-Pad4)") (class "Default")
      (node (ref "PWROUT") (pin "4") (pinfunction "KL_4") (pintype "passive"))
    )
  )
)
